# encoder_motor.net
KiCad netlist of a schematic drawn in Altium Designer
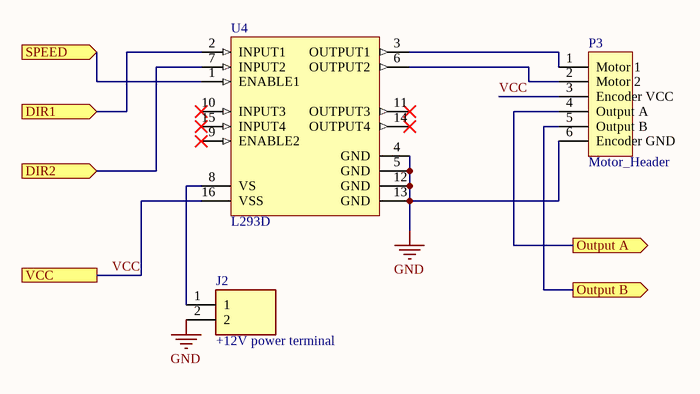
[diagram p0: encoder_motor.SchDoc]

(export (version "E")
  (design (tool "Eeschema 10.0.6"))
  (components
    (comp (ref "J2")
      (value "+12V power terminal")
      (footprint "screw_terminal")
      (description "2~24 Poles, Screw Type, Horizontal, 5.0 Pitch, 22~12 (AWG), Terminal Block Connector")
      (fields (field (name "MP") "TB002-500-02BE") (field (name "MF") "CUI Devices"))
      (libsource (lib "TB002-500-02BE") (part "TB002-500-02BE"))
    )
    (comp (ref "P3")
      (value "Motor_Header")
      (footprint "HDR1X6")
      (description "Header, 6-Pin")
      (fields (field (name "PUBLISHER") "Altium Limited"))
      (libsource (lib "Miscellaneous Connectors") (part "Header 6"))
    )
    (comp (ref "U4")
      (value "L293D")
      (footprint "STM-L293D-16")
      (description "Push-Pull Four Channel Driver with Diode, 4.5 to 36 V, -40 to 150 degC, 16-Pin PDIP, RoHS, Tube")
      (fields (field (name "MANUFACTURER") "STMicroelectronics"))
      (libsource (lib "Altium Content Vault") (part "STM-L293D-16"))
    )
  )
  (nets
    (net (code "1") (name "/DIR1") (class "Default")
      (node (ref "U4") (pin "2") (pinfunction "INPUT1_2") (pintype "input"))
    )
    (net (code "2") (name "/DIR2") (class "Default")
      (node (ref "U4") (pin "7") (pinfunction "INPUT2_7") (pintype "input"))
    )
    (net (code "3") (name "/Output A") (class "Default")
      (node (ref "P3") (pin "4") (pinfunction "Output_A_4") (pintype "passive"))
    )
    (net (code "4") (name "/Output B") (class "Default")
      (node (ref "P3") (pin "5") (pinfunction "Output_B_5") (pintype "passive"))
    )
    (net (code "5") (name "/SPEED") (class "Default")
      (node (ref "U4") (pin "1") (pinfunction "ENABLE1_1") (pintype "input"))
    )
    (net (code "6") (name "/VCC") (class "Default")
      (node (ref "P3") (pin "3") (pinfunction "Encoder_VCC_3") (pintype "passive"))
      (node (ref "U4") (pin "16") (pinfunction "VSS_16") (pintype "power_in"))
    )
    (net (code "7") (name "GND") (class "Default")
      (node (ref "J2") (pin "2") (pinfunction "2_2") (pintype "passive"))
      (node (ref "P3") (pin "6") (pinfunction "Encoder_GND_6") (pintype "passive"))
      (node (ref "U4") (pin "12") (pinfunction "GND_12") (pintype "power_in"))
      (node (ref "U4") (pin "13") (pinfunction "GND_13") (pintype "power_in"))
      (node (ref "U4") (pin "4") (pinfunction "GND_4") (pintype "power_in"))
      (node (ref "U4") (pin "5") (pinfunction "GND_5") (pintype "power_in"))
    )
    (net (code "8") (name "Net-(P3-Motor_1)") (class "Default")
      (node (ref "P3") (pin "1") (pinfunction "Motor_1_1") (pintype "passive"))
      (node (ref "U4") (pin "3") (pinfunction "OUTPUT1_3") (pintype "output"))
    )
    (net (code "9") (name "Net-(P3-Motor_2)") (class "Default")
      (node (ref "P3") (pin "2") (pinfunction "Motor_2_2") (pintype "passive"))
      (node (ref "U4") (pin "6") (pinfunction "OUTPUT2_6") (pintype "output"))
    )
    (net (code "10") (name "Net-(U4-VS)") (class "Default")
      (node (ref "J2") (pin "1") (pinfunction "1_1") (pintype "passive"))
      (node (ref "U4") (pin "8") (pinfunction "VS_8") (pintype "power_in"))
    )
    (net (code "11") (name "unconnected-(U4-ENABLE2-Pad9)") (class "Default")
      (node (ref "U4") (pin "9") (pinfunction "ENABLE2_9") (pintype "input+no_connect"))
    )
    (net (code "12") (name "unconnected-(U4-INPUT3-Pad10)") (class "Default")
      (node (ref "U4") (pin "10") (pinfunction "INPUT3_10") (pintype "input+no_connect"))
    )
    (net (code "13") (name "unconnected-(U4-INPUT4-Pad15)") (class "Default")
      (node (ref "U4") (pin "15") (pinfunction "INPUT4_15") (pintype "input+no_connect"))
    )
    (net (code "14") (name "unconnected-(U4-OUTPUT3-Pad11)") (class "Default")
      (node (ref "U4") (pin "11") (pinfunction "OUTPUT3_11") (pintype "output+no_connect"))
    )
    (net (code "15") (name "unconnected-(U4-OUTPUT4-Pad14)") (class "Default")
      (node (ref "U4") (pin "14") (pinfunction "OUTPUT4_14") (pintype "output+no_connect"))
    )
  )
)
